# Sheet1.net
KiCad netlist of a schematic drawn in Altium Designer
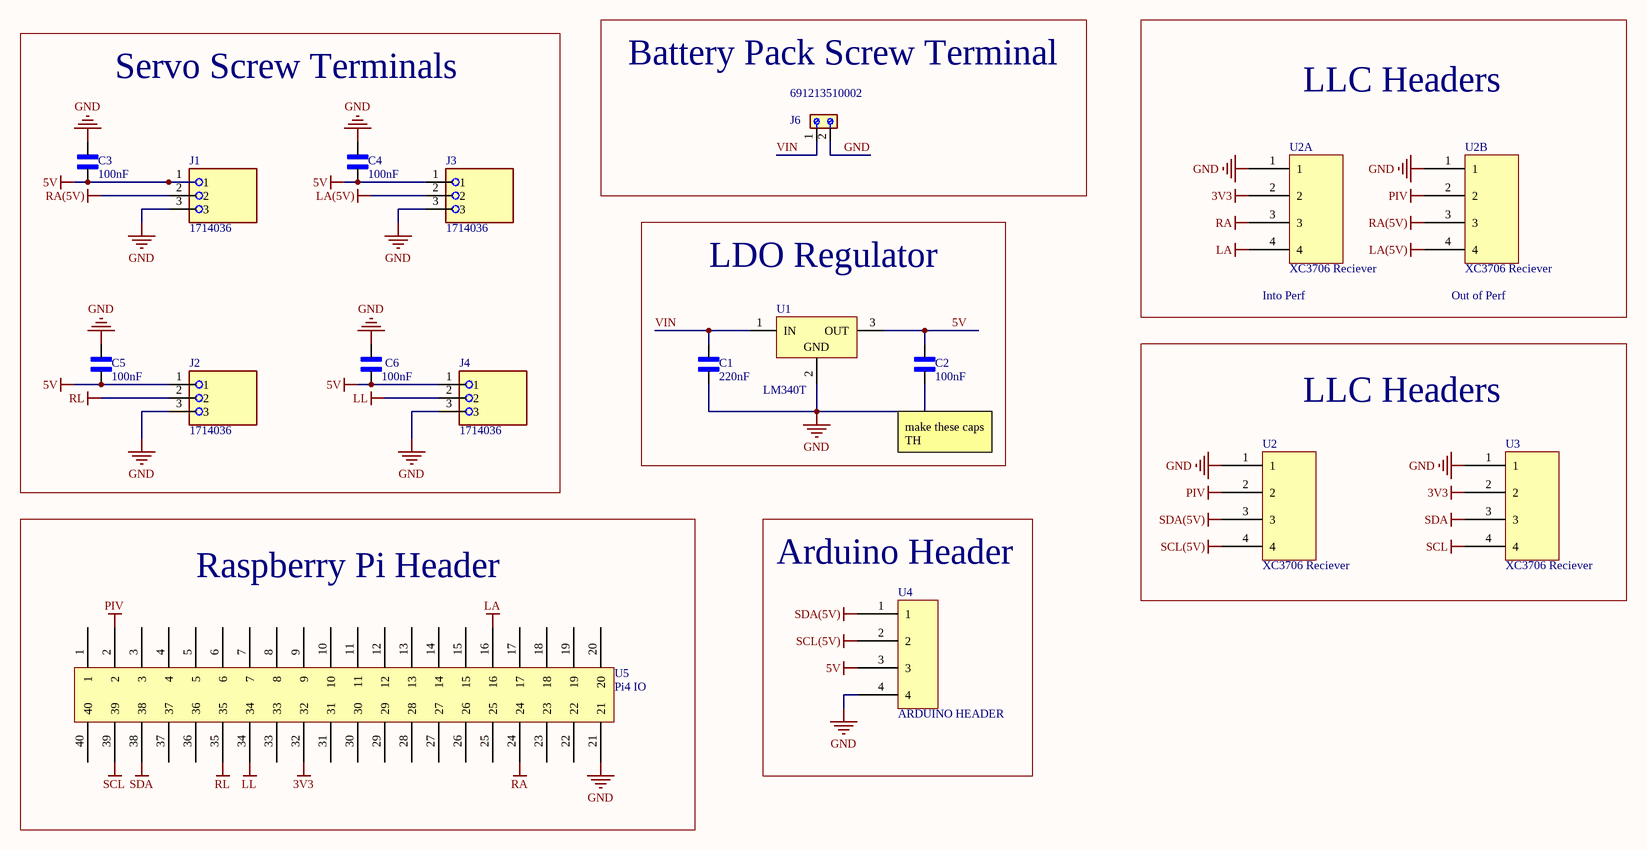
[diagram p0: Sheet1.SchDoc]

(export (version "E")
  (design (tool "Eeschema 10.0.6"))
  (components
    (comp (ref "C1")
      (value "220nF")
      (footprint "CAPRR508W50L508T317H508")
      (description "SR 220nF Ceramic Multilayer Cap,50V dc,+85C,Z5U Dielectric,+/-20%,Through Hole")
      (fields (field (name "MP") "SR215E224MARTR") (field (name "MF") "KYOCERA AVX"))
      (libsource (lib "lonelyjelly84") (part "SR215E224MARTR"))
    )
    (comp (ref "C2")
      (value "100nF")
      (footprint "CAPRR254W50L508T317H508")
      (description "SR 100nF Ceramic Multilayer Cap,100V dc,+85C,Z5U Dielectric,+/-20%,Through Hole")
      (fields (field (name "MF") "KYOCERA AVX") (field (name "MP") "SR201E104MARTR"))
      (libsource (lib "lonelyjelly84") (part "SR201E104MARTR"))
    )
    (comp (ref "C3")
      (value "100nF")
      (footprint "CAPRR254W50L508T317H508")
      (description "SR 100nF Ceramic Multilayer Cap,100V dc,+85C,Z5U Dielectric,+/-20%,Through Hole")
      (fields (field (name "MF") "KYOCERA AVX") (field (name "MP") "SR201E104MARTR"))
      (libsource (lib "lonelyjelly84") (part "SR201E104MARTR"))
    )
    (comp (ref "C4")
      (value "100nF")
      (footprint "CAPRR254W50L508T317H508")
      (description "SR 100nF Ceramic Multilayer Cap,100V dc,+85C,Z5U Dielectric,+/-20%,Through Hole")
      (fields (field (name "MF") "KYOCERA AVX") (field (name "MP") "SR201E104MARTR"))
      (libsource (lib "lonelyjelly84") (part "SR201E104MARTR"))
    )
    (comp (ref "C5")
      (value "100nF")
      (footprint "CAPRR254W50L508T317H508")
      (description "SR 100nF Ceramic Multilayer Cap,100V dc,+85C,Z5U Dielectric,+/-20%,Through Hole")
      (fields (field (name "MF") "KYOCERA AVX") (field (name "MP") "SR201E104MARTR"))
      (libsource (lib "lonelyjelly84") (part "SR201E104MARTR"))
    )
    (comp (ref "C6")
      (value "100nF")
      (footprint "CAPRR254W50L508T317H508")
      (description "SR 100nF Ceramic Multilayer Cap,100V dc,+85C,Z5U Dielectric,+/-20%,Through Hole")
      (fields (field (name "MF") "KYOCERA AVX") (field (name "MP") "SR201E104MARTR"))
      (libsource (lib "lonelyjelly84") (part "SR201E104MARTR"))
    )
    (comp (ref "J1")
      (value "1714036")
      (footprint "PHOENIX_1714036")
      (description "PCB Terminal Screw 5mm 12AWG 400V 24A 3 Position COMBICON MKDSP Series")
      (fields (field (name "MF") "Phoenix Contact"))
      (libsource (lib "lonelyjelly84") (part "1714036"))
    )
    (comp (ref "J2")
      (value "1714036")
      (footprint "PHOENIX_1714036")
      (description "PCB Terminal Screw 5mm 12AWG 400V 24A 3 Position COMBICON MKDSP Series")
      (fields (field (name "MF") "Phoenix Contact"))
      (libsource (lib "lonelyjelly84") (part "1714036"))
    )
    (comp (ref "J3")
      (value "1714036")
      (footprint "PHOENIX_1714036")
      (description "PCB Terminal Screw 5mm 12AWG 400V 24A 3 Position COMBICON MKDSP Series")
      (fields (field (name "MF") "Phoenix Contact"))
      (libsource (lib "lonelyjelly84") (part "1714036"))
    )
    (comp (ref "J4")
      (value "1714036")
      (footprint "PHOENIX_1714036")
      (description "PCB Terminal Screw 5mm 12AWG 400V 24A 3 Position COMBICON MKDSP Series")
      (fields (field (name "MF") "Phoenix Contact"))
      (libsource (lib "lonelyjelly84") (part "1714036"))
    )
    (comp (ref "J6")
      (value "691213510002")
      (footprint "691213510002")
      (description "2 Position Wire to Board Terminal Block Horizontal with Board 0.200 (5.08mm) Through Hole")
      (fields (field (name "MF") "WÃ¼rth Elektronik"))
      (libsource (lib "lonelyjelly84") (part "691213510002"))
    )
    (comp (ref "U1")
      (value "LM340T")
      (footprint "NDE0003A")
      (description "Pwr Sply Func, Voltage Regulator, Positive Voltage Out, TO-220, IS 6mA, VO 5V, Vn 40uV")
      (libsource (lib "lonelyjelly84") (part "PM-REG-LM2940-SIL3"))
    )
    (comp (ref "U2")
      (value "XC3706 Reciever")
      (footprint "XC3706 Reciever")
      (libsource (lib "ISP") (part "XC3706 Reciever"))
    )
    (comp (ref "U2A")
      (value "XC3706 Reciever")
      (footprint "XC3706 Reciever")
      (libsource (lib "ISP") (part "XC3706 Reciever"))
    )
    (comp (ref "U2B")
      (value "XC3706 Reciever")
      (footprint "XC3706 Reciever")
      (libsource (lib "ISP") (part "XC3706 Reciever"))
    )
    (comp (ref "U3")
      (value "XC3706 Reciever")
      (footprint "XC3706 Reciever")
      (libsource (lib "ISP") (part "XC3706 Reciever"))
    )
    (comp (ref "U4")
      (value "ARDUINO HEADER")
      (footprint "ARDUINO HEADER")
      (libsource (lib "ISP") (part "ARDUINO HEADER"))
    )
    (comp (ref "U5") (value "Pi4 IO") (footprint "PI4 GPIO") (libsource (lib "ISP") (part "Pi4 IO")))
  )
  (nets
    (net (code "1") (name "/VIN") (class "Default")
      (node (ref "C1") (pin "2") (pinfunction "2_2") (pintype "passive"))
      (node (ref "J6") (pin "1") (pinfunction "1_1") (pintype "passive"))
      (node (ref "U1") (pin "1") (pinfunction "IN_1") (pintype "power_in"))
    )
    (net (code "2") (name "3V3") (class "Default")
      (node (ref "U2A") (pin "2") (pinfunction "2_2") (pintype "passive"))
      (node (ref "U3") (pin "2") (pinfunction "2_2") (pintype "passive"))
      (node (ref "U5") (pin "32") (pinfunction "32_32") (pintype "passive"))
    )
    (net (code "3") (name "5V") (class "Default")
      (node (ref "C2") (pin "1") (pinfunction "1_1") (pintype "passive"))
      (node (ref "C3") (pin "2") (pinfunction "2_2") (pintype "passive"))
      (node (ref "C4") (pin "2") (pinfunction "2_2") (pintype "passive"))
      (node (ref "C5") (pin "2") (pinfunction "2_2") (pintype "passive"))
      (node (ref "C6") (pin "2") (pinfunction "2_2") (pintype "passive"))
      (node (ref "J1") (pin "1") (pinfunction "1_1") (pintype "passive"))
      (node (ref "J2") (pin "1") (pinfunction "1_1") (pintype "passive"))
      (node (ref "J3") (pin "1") (pinfunction "1_1") (pintype "passive"))
      (node (ref "J4") (pin "1") (pinfunction "1_1") (pintype "passive"))
      (node (ref "U1") (pin "3") (pinfunction "OUT_3") (pintype "power_in"))
      (node (ref "U4") (pin "3") (pinfunction "3_3") (pintype "passive"))
    )
    (net (code "4") (name "GND") (class "Default")
      (node (ref "C1") (pin "1") (pinfunction "1_1") (pintype "passive"))
      (node (ref "C2") (pin "2") (pinfunction "2_2") (pintype "passive"))
      (node (ref "C3") (pin "1") (pinfunction "1_1") (pintype "passive"))
      (node (ref "C4") (pin "1") (pinfunction "1_1") (pintype "passive"))
      (node (ref "C5") (pin "1") (pinfunction "1_1") (pintype "passive"))
      (node (ref "C6") (pin "1") (pinfunction "1_1") (pintype "passive"))
      (node (ref "J1") (pin "3") (pinfunction "3_3") (pintype "passive"))
      (node (ref "J2") (pin "3") (pinfunction "3_3") (pintype "passive"))
      (node (ref "J3") (pin "3") (pinfunction "3_3") (pintype "passive"))
      (node (ref "J4") (pin "3") (pinfunction "3_3") (pintype "passive"))
      (node (ref "J6") (pin "2") (pinfunction "2_2") (pintype "passive"))
      (node (ref "U1") (pin "2") (pinfunction "GND_2") (pintype "power_in"))
      (node (ref "U2") (pin "1") (pinfunction "1_1") (pintype "passive"))
      (node (ref "U2A") (pin "1") (pinfunction "1_1") (pintype "passive"))
      (node (ref "U2B") (pin "1") (pinfunction "1_1") (pintype "passive"))
      (node (ref "U3") (pin "1") (pinfunction "1_1") (pintype "passive"))
      (node (ref "U4") (pin "4") (pinfunction "4_4") (pintype "passive"))
      (node (ref "U5") (pin "21") (pinfunction "21_21") (pintype "passive"))
    )
    (net (code "5") (name "LA") (class "Default")
      (node (ref "U2A") (pin "4") (pinfunction "4_4") (pintype "passive"))
      (node (ref "U5") (pin "16") (pinfunction "16_16") (pintype "passive"))
    )
    (net (code "6") (name "LA(5V)") (class "Default")
      (node (ref "J3") (pin "2") (pinfunction "2_2") (pintype "passive"))
      (node (ref "U2B") (pin "4") (pinfunction "4_4") (pintype "passive"))
    )
    (net (code "7") (name "LL") (class "Default")
      (node (ref "J4") (pin "2") (pinfunction "2_2") (pintype "passive"))
      (node (ref "U5") (pin "34") (pinfunction "34_34") (pintype "passive"))
    )
    (net (code "8") (name "PIV") (class "Default")
      (node (ref "U2") (pin "2") (pinfunction "2_2") (pintype "passive"))
      (node (ref "U2B") (pin "2") (pinfunction "2_2") (pintype "passive"))
      (node (ref "U5") (pin "2") (pinfunction "2_2") (pintype "passive"))
    )
    (net (code "9") (name "RA") (class "Default")
      (node (ref "U2A") (pin "3") (pinfunction "3_3") (pintype "passive"))
      (node (ref "U5") (pin "24") (pinfunction "24_24") (pintype "passive"))
    )
    (net (code "10") (name "RA(5V)") (class "Default")
      (node (ref "J1") (pin "2") (pinfunction "2_2") (pintype "passive"))
      (node (ref "U2B") (pin "3") (pinfunction "3_3") (pintype "passive"))
    )
    (net (code "11") (name "RL") (class "Default")
      (node (ref "J2") (pin "2") (pinfunction "2_2") (pintype "passive"))
      (node (ref "U5") (pin "35") (pinfunction "35_35") (pintype "passive"))
    )
    (net (code "12") (name "SCL") (class "Default")
      (node (ref "U3") (pin "4") (pinfunction "4_4") (pintype "passive"))
      (node (ref "U5") (pin "39") (pinfunction "39_39") (pintype "passive"))
    )
    (net (code "13") (name "SCL(5V)") (class "Default")
      (node (ref "U2") (pin "4") (pinfunction "4_4") (pintype "passive"))
      (node (ref "U4") (pin "2") (pinfunction "2_2") (pintype "passive"))
    )
    (net (code "14") (name "SDA") (class "Default")
      (node (ref "U3") (pin "3") (pinfunction "3_3") (pintype "passive"))
      (node (ref "U5") (pin "38") (pinfunction "38_38") (pintype "passive"))
    )
    (net (code "15") (name "SDA(5V)") (class "Default")
      (node (ref "U2") (pin "3") (pinfunction "3_3") (pintype "passive"))
      (node (ref "U4") (pin "1") (pinfunction "1_1") (pintype "passive"))
    )
    (net (code "16") (name "unconnected-(U5-Pad1)") (class "Default")
      (node (ref "U5") (pin "1") (pinfunction "1_1") (pintype "passive"))
    )
    (net (code "17") (name "unconnected-(U5-Pad3)") (class "Default")
      (node (ref "U5") (pin "3") (pinfunction "3_3") (pintype "passive"))
    )
    (net (code "18") (name "unconnected-(U5-Pad4)") (class "Default")
      (node (ref "U5") (pin "4") (pinfunction "4_4") (pintype "passive"))
    )
    (net (code "19") (name "unconnected-(U5-Pad5)") (class "Default")
      (node (ref "U5") (pin "5") (pinfunction "5_5") (pintype "passive"))
    )
    (net (code "20") (name "unconnected-(U5-Pad6)") (class "Default")
      (node (ref "U5") (pin "6") (pinfunction "6_6") (pintype "passive"))
    )
    (net (code "21") (name "unconnected-(U5-Pad7)") (class "Default")
      (node (ref "U5") (pin "7") (pinfunction "7_7") (pintype "passive"))
    )
    (net (code "22") (name "unconnected-(U5-Pad8)") (class "Default")
      (node (ref "U5") (pin "8") (pinfunction "8_8") (pintype "passive"))
    )
    (net (code "23") (name "unconnected-(U5-Pad9)") (class "Default")
      (node (ref "U5") (pin "9") (pinfunction "9_9") (pintype "passive"))
    )
    (net (code "24") (name "unconnected-(U5-Pad10)") (class "Default")
      (node (ref "U5") (pin "10") (pinfunction "10_10") (pintype "passive"))
    )
    (net (code "25") (name "unconnected-(U5-Pad11)") (class "Default")
      (node (ref "U5") (pin "11") (pinfunction "11_11") (pintype "passive"))
    )
    (net (code "26") (name "unconnected-(U5-Pad12)") (class "Default")
      (node (ref "U5") (pin "12") (pinfunction "12_12") (pintype "passive"))
    )
    (net (code "27") (name "unconnected-(U5-Pad13)") (class "Default")
      (node (ref "U5") (pin "13") (pinfunction "13_13") (pintype "passive"))
    )
    (net (code "28") (name "unconnected-(U5-Pad14)") (class "Default")
      (node (ref "U5") (pin "14") (pinfunction "14_14") (pintype "passive"))
    )
    (net (code "29") (name "unconnected-(U5-Pad15)") (class "Default")
      (node (ref "U5") (pin "15") (pinfunction "15_15") (pintype "passive"))
    )
    (net (code "30") (name "unconnected-(U5-Pad17)") (class "Default")
      (node (ref "U5") (pin "17") (pinfunction "17_17") (pintype "passive"))
    )
    (net (code "31") (name "unconnected-(U5-Pad18)") (class "Default")
      (node (ref "U5") (pin "18") (pinfunction "18_18") (pintype "passive"))
    )
    (net (code "32") (name "unconnected-(U5-Pad19)") (class "Default")
      (node (ref "U5") (pin "19") (pinfunction "19_19") (pintype "passive"))
    )
    (net (code "33") (name "unconnected-(U5-Pad20)") (class "Default")
      (node (ref "U5") (pin "20") (pinfunction "20_20") (pintype "passive"))
    )
    (net (code "34") (name "unconnected-(U5-Pad22)") (class "Default")
      (node (ref "U5") (pin "22") (pinfunction "22_22") (pintype "passive"))
    )
    (net (code "35") (name "unconnected-(U5-Pad23)") (class "Default")
      (node (ref "U5") (pin "23") (pinfunction "23_23") (pintype "passive"))
    )
    (net (code "36") (name "unconnected-(U5-Pad25)") (class "Default")
      (node (ref "U5") (pin "25") (pinfunction "25_25") (pintype "passive"))
    )
    (net (code "37") (name "unconnected-(U5-Pad26)") (class "Default")
      (node (ref "U5") (pin "26") (pinfunction "26_26") (pintype "passive"))
    )
    (net (code "38") (name "unconnected-(U5-Pad27)") (class "Default")
      (node (ref "U5") (pin "27") (pinfunction "27_27") (pintype "passive"))
    )
    (net (code "39") (name "unconnected-(U5-Pad28)") (class "Default")
      (node (ref "U5") (pin "28") (pinfunction "28_28") (pintype "passive"))
    )
    (net (code "40") (name "unconnected-(U5-Pad29)") (class "Default")
      (node (ref "U5") (pin "29") (pinfunction "29_29") (pintype "passive"))
    )
    (net (code "41") (name "unconnected-(U5-Pad30)") (class "Default")
      (node (ref "U5") (pin "30") (pinfunction "30_30") (pintype "passive"))
    )
    (net (code "42") (name "unconnected-(U5-Pad31)") (class "Default")
      (node (ref "U5") (pin "31") (pinfunction "31_31") (pintype "passive"))
    )
    (net (code "43") (name "unconnected-(U5-Pad33)") (class "Default")
      (node (ref "U5") (pin "33") (pinfunction "33_33") (pintype "passive"))
    )
    (net (code "44") (name "unconnected-(U5-Pad36)") (class "Default")
      (node (ref "U5") (pin "36") (pinfunction "36_36") (pintype "passive"))
    )
    (net (code "45") (name "unconnected-(U5-Pad37)") (class "Default")
      (node (ref "U5") (pin "37") (pinfunction "37_37") (pintype "passive"))
    )
    (net (code "46") (name "unconnected-(U5-Pad40)") (class "Default")
      (node (ref "U5") (pin "40") (pinfunction "40_40") (pintype "passive"))
    )
  )
)
